# rrfdc.net
KiCad netlist of a schematic drawn in EAGLE
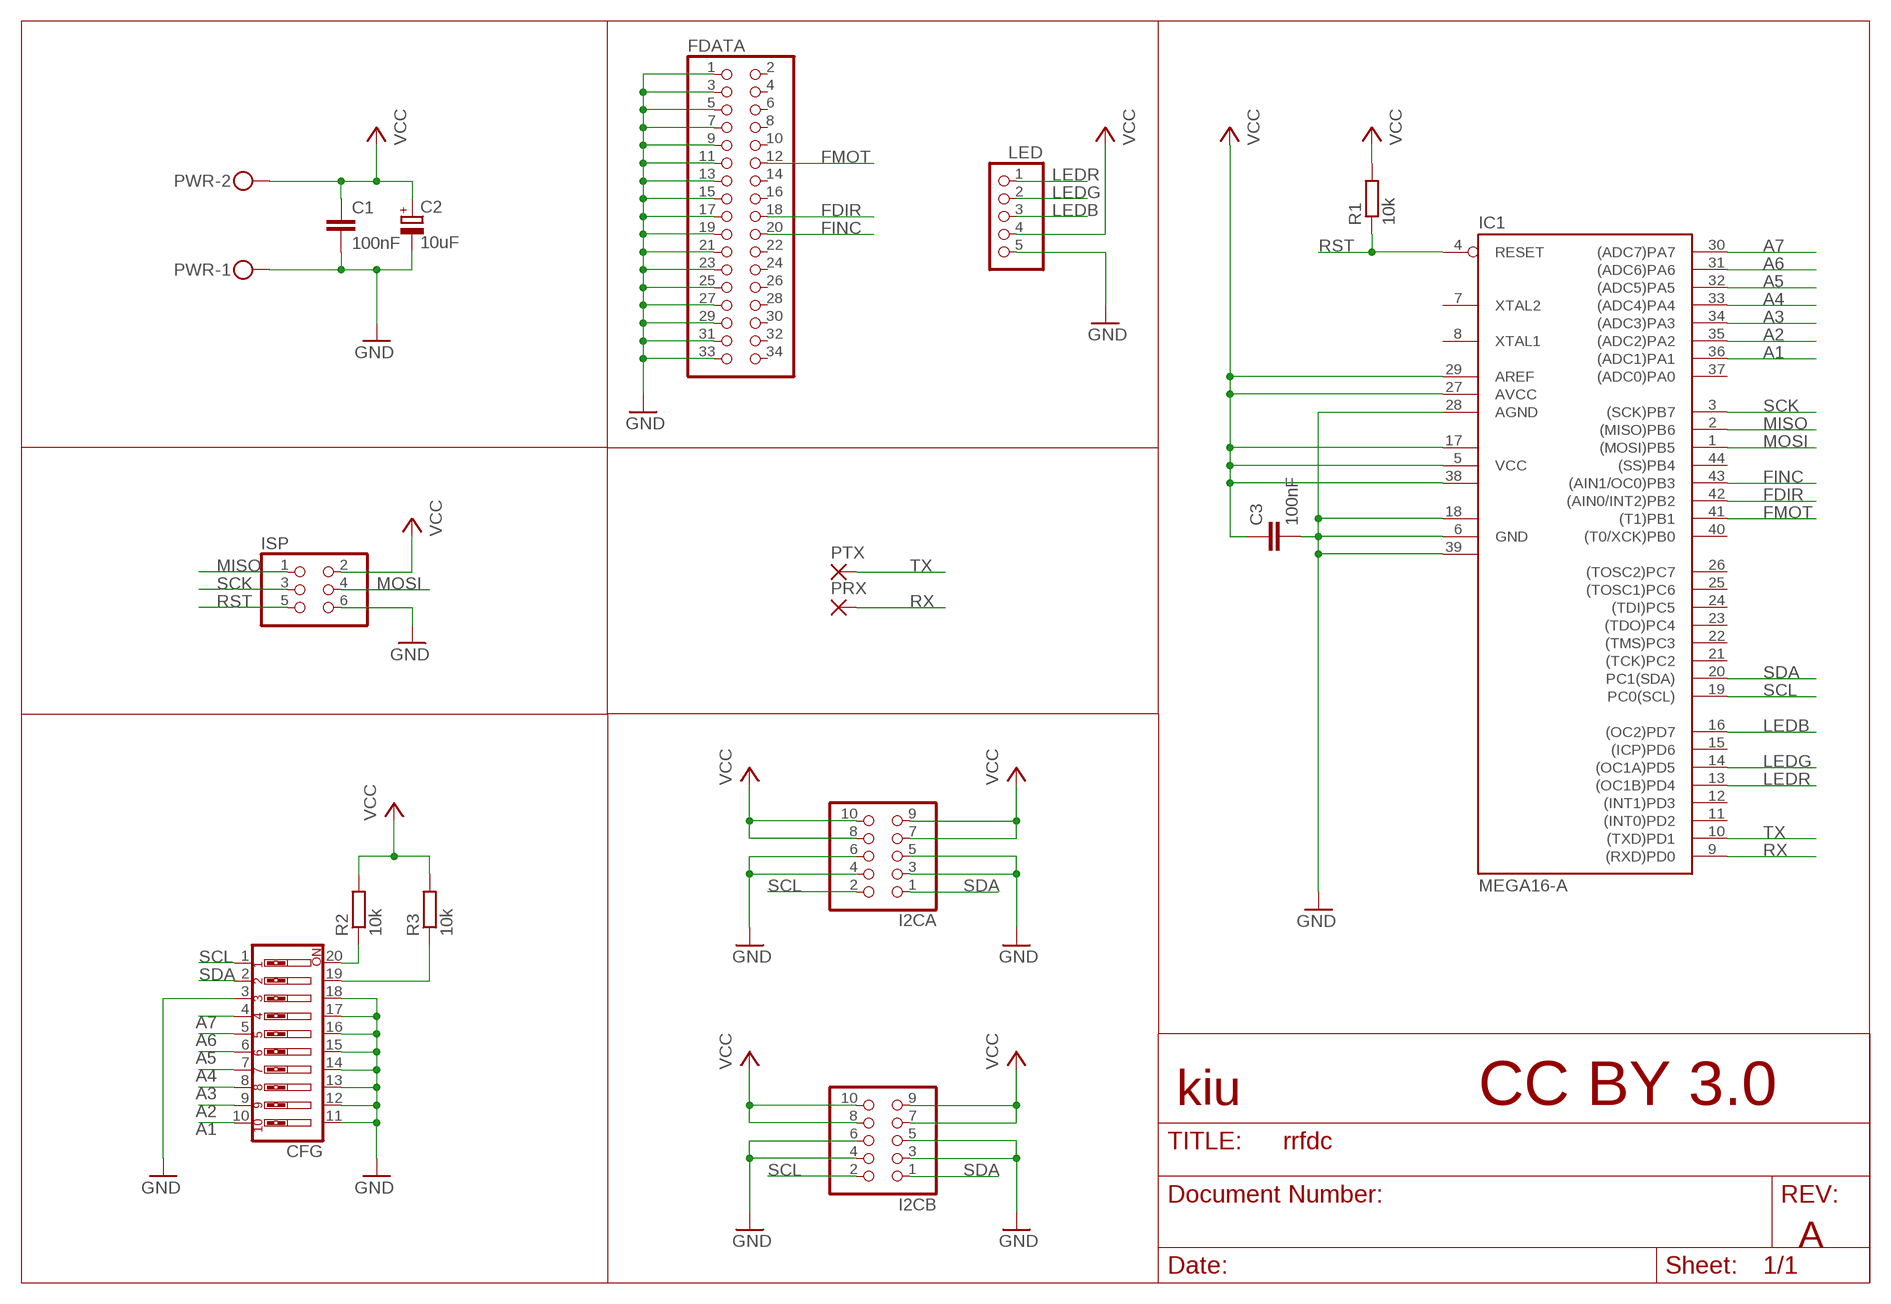
[diagram p0: schematic, sheet 1]

(export (version "E")
  (design (tool "Eeschema 10.0.6"))
  (components
    (comp (ref "C1")
      (value "100nF")
      (footprint "eagle-import:C0805")
      (libsource (lib "eagle-import") (part "C-EUC0805"))
    )
    (comp (ref "C2")
      (value "10uF")
      (footprint "eagle-import:CT3216")
      (libsource (lib "eagle-import") (part "CPOL-EUCT3216"))
    )
    (comp (ref "C3")
      (value "100nF")
      (footprint "eagle-import:C0805")
      (libsource (lib "eagle-import") (part "C-EUC0805"))
    )
    (comp (ref "CFG")
      (value "SW_DIP-10")
      (footprint "eagle-import:EDG-10")
      (libsource (lib "eagle-import") (part "SW_DIP-10"))
    )
    (comp (ref "FDATA")
      (value "PINHD-2X17")
      (footprint "eagle-import:2X17")
      (libsource (lib "eagle-import") (part "PINHD-2X17"))
    )
    (comp (ref "I2CA")
      (value "PINHD-2X5")
      (footprint "eagle-import:2X05")
      (libsource (lib "eagle-import") (part "PINHD-2X5"))
    )
    (comp (ref "I2CB")
      (value "PINHD-2X5")
      (footprint "eagle-import:2X05")
      (libsource (lib "eagle-import") (part "PINHD-2X5"))
    )
    (comp (ref "IC1")
      (value "MEGA16-A")
      (footprint "eagle-import:TQFP44")
      (libsource (lib "eagle-import") (part "MEGA16-A"))
    )
    (comp (ref "ISP")
      (value "PINHD-2X3")
      (footprint "eagle-import:2X03")
      (libsource (lib "eagle-import") (part "PINHD-2X3"))
    )
    (comp (ref "LED")
      (value "PINHD-1X5")
      (footprint "eagle-import:1X05")
      (libsource (lib "eagle-import") (part "PINHD-1X5"))
    )
    (comp (ref "PRX")
      (value "SMD2")
      (footprint "eagle-import:SMD1,27-2,54")
      (libsource (lib "eagle-import") (part "SMD2"))
    )
    (comp (ref "PTX")
      (value "SMD2")
      (footprint "eagle-import:SMD1,27-2,54")
      (libsource (lib "eagle-import") (part "SMD2"))
    )
    (comp (ref "PWR")
      (value "MKDSN1,5/2-5,08")
      (footprint "eagle-import:MKDSN1,5_2-5,08")
      (fields (field (name "MPN") "MKDSN 1,5/2-5.08"))
      (libsource (lib "eagle-import") (part "MKDSN1,5/2-5,08"))
    )
    (comp (ref "R1")
      (value "10k")
      (footprint "eagle-import:R0805")
      (libsource (lib "eagle-import") (part "R-EU_R0805"))
    )
    (comp (ref "R2")
      (value "10k")
      (footprint "eagle-import:R0805")
      (libsource (lib "eagle-import") (part "R-EU_R0805"))
    )
    (comp (ref "R3")
      (value "10k")
      (footprint "eagle-import:R0805")
      (libsource (lib "eagle-import") (part "R-EU_R0805"))
    )
  )
  (nets
    (net (code "1") (name "/A1") (class "Default")
      (node (ref "CFG") (pin "10") (pinfunction "10_10") (pintype "passive"))
      (node (ref "IC1") (pin "36") (pinfunction "(ADC1)PA1_36") (pintype "bidirectional"))
    )
    (net (code "2") (name "/A2") (class "Default")
      (node (ref "CFG") (pin "9") (pinfunction "9_9") (pintype "passive"))
      (node (ref "IC1") (pin "35") (pinfunction "(ADC2)PA2_35") (pintype "bidirectional"))
    )
    (net (code "3") (name "/A3") (class "Default")
      (node (ref "CFG") (pin "8") (pinfunction "8_8") (pintype "passive"))
      (node (ref "IC1") (pin "34") (pinfunction "(ADC3)PA3_34") (pintype "bidirectional"))
    )
    (net (code "4") (name "/A4") (class "Default")
      (node (ref "CFG") (pin "7") (pinfunction "7_7") (pintype "passive"))
      (node (ref "IC1") (pin "33") (pinfunction "(ADC4)PA4_33") (pintype "bidirectional"))
    )
    (net (code "5") (name "/A5") (class "Default")
      (node (ref "CFG") (pin "6") (pinfunction "6_6") (pintype "passive"))
      (node (ref "IC1") (pin "32") (pinfunction "(ADC5)PA5_32") (pintype "bidirectional"))
    )
    (net (code "6") (name "/A6") (class "Default")
      (node (ref "CFG") (pin "5") (pinfunction "5_5") (pintype "passive"))
      (node (ref "IC1") (pin "31") (pinfunction "(ADC6)PA6_31") (pintype "bidirectional"))
    )
    (net (code "7") (name "/A7") (class "Default")
      (node (ref "CFG") (pin "4") (pinfunction "4_4") (pintype "passive"))
      (node (ref "IC1") (pin "30") (pinfunction "(ADC7)PA7_30") (pintype "bidirectional"))
    )
    (net (code "8") (name "/FDIR") (class "Default")
      (node (ref "FDATA") (pin "18") (pinfunction "18_18") (pintype "passive"))
      (node (ref "IC1") (pin "42") (pinfunction "(AIN0/INT2)PB2_42") (pintype "bidirectional"))
    )
    (net (code "9") (name "/FINC") (class "Default")
      (node (ref "FDATA") (pin "20") (pinfunction "20_20") (pintype "passive"))
      (node (ref "IC1") (pin "43") (pinfunction "(AIN1/OC0)PB3_43") (pintype "bidirectional"))
    )
    (net (code "10") (name "/FMOT") (class "Default")
      (node (ref "FDATA") (pin "12") (pinfunction "12_12") (pintype "passive"))
      (node (ref "IC1") (pin "41") (pinfunction "(T1)PB1_41") (pintype "bidirectional"))
    )
    (net (code "11") (name "/LEDB") (class "Default")
      (node (ref "IC1") (pin "16") (pinfunction "(OC2)PD7_16") (pintype "bidirectional"))
      (node (ref "LED") (pin "3") (pinfunction "3_3") (pintype "passive"))
    )
    (net (code "12") (name "/LEDG") (class "Default")
      (node (ref "IC1") (pin "14") (pinfunction "(OC1A)PD5_14") (pintype "bidirectional"))
      (node (ref "LED") (pin "2") (pinfunction "2_2") (pintype "passive"))
    )
    (net (code "13") (name "/LEDR") (class "Default")
      (node (ref "IC1") (pin "13") (pinfunction "(OC1B)PD4_13") (pintype "bidirectional"))
      (node (ref "LED") (pin "1") (pinfunction "1_1") (pintype "passive"))
    )
    (net (code "14") (name "/MISO") (class "Default")
      (node (ref "IC1") (pin "2") (pinfunction "(MISO)PB6_2") (pintype "bidirectional"))
      (node (ref "ISP") (pin "1") (pinfunction "1_1") (pintype "passive"))
    )
    (net (code "15") (name "/MOSI") (class "Default")
      (node (ref "IC1") (pin "1") (pinfunction "(MOSI)PB5_1") (pintype "bidirectional"))
      (node (ref "ISP") (pin "4") (pinfunction "4_4") (pintype "passive"))
    )
    (net (code "16") (name "/RST") (class "Default")
      (node (ref "IC1") (pin "4") (pinfunction "RESET_4") (pintype "input"))
      (node (ref "ISP") (pin "5") (pinfunction "5_5") (pintype "passive"))
      (node (ref "R1") (pin "1") (pinfunction "1_1") (pintype "passive"))
    )
    (net (code "17") (name "/RX") (class "Default")
      (node (ref "IC1") (pin "9") (pinfunction "(RXD)PD0_9") (pintype "bidirectional"))
      (node (ref "PRX") (pin "1") (pinfunction "P_1") (pintype "passive"))
    )
    (net (code "18") (name "/SCK") (class "Default")
      (node (ref "IC1") (pin "3") (pinfunction "(SCK)PB7_3") (pintype "bidirectional"))
      (node (ref "ISP") (pin "3") (pinfunction "3_3") (pintype "passive"))
    )
    (net (code "19") (name "/SCL") (class "Default")
      (node (ref "CFG") (pin "1") (pinfunction "1_1") (pintype "passive"))
      (node (ref "I2CA") (pin "2") (pinfunction "2_2") (pintype "passive"))
      (node (ref "I2CB") (pin "2") (pinfunction "2_2") (pintype "passive"))
      (node (ref "IC1") (pin "19") (pinfunction "PC0(SCL)_19") (pintype "bidirectional"))
    )
    (net (code "20") (name "/SDA") (class "Default")
      (node (ref "CFG") (pin "2") (pinfunction "2_2") (pintype "passive"))
      (node (ref "I2CA") (pin "1") (pinfunction "1_1") (pintype "passive"))
      (node (ref "I2CB") (pin "1") (pinfunction "1_1") (pintype "passive"))
      (node (ref "IC1") (pin "20") (pinfunction "PC1(SDA)_20") (pintype "bidirectional"))
    )
    (net (code "21") (name "/TX") (class "Default")
      (node (ref "IC1") (pin "10") (pinfunction "(TXD)PD1_10") (pintype "bidirectional"))
      (node (ref "PTX") (pin "1") (pinfunction "P_1") (pintype "passive"))
    )
    (net (code "22") (name "GND") (class "Default")
      (node (ref "C1") (pin "2") (pinfunction "2_2") (pintype "passive"))
      (node (ref "C2") (pin "-") (pinfunction "-_-") (pintype "passive"))
      (node (ref "C3") (pin "2") (pinfunction "2_2") (pintype "passive"))
      (node (ref "CFG") (pin "11") (pinfunction "11_11") (pintype "passive"))
      (node (ref "CFG") (pin "12") (pinfunction "12_12") (pintype "passive"))
      (node (ref "CFG") (pin "13") (pinfunction "13_13") (pintype "passive"))
      (node (ref "CFG") (pin "14") (pinfunction "14_14") (pintype "passive"))
      (node (ref "CFG") (pin "15") (pinfunction "15_15") (pintype "passive"))
      (node (ref "CFG") (pin "16") (pinfunction "16_16") (pintype "passive"))
      (node (ref "CFG") (pin "17") (pinfunction "17_17") (pintype "passive"))
      (node (ref "CFG") (pin "18") (pinfunction "18_18") (pintype "passive"))
      (node (ref "CFG") (pin "3") (pinfunction "3_3") (pintype "passive"))
      (node (ref "FDATA") (pin "1") (pinfunction "1_1") (pintype "passive"))
      (node (ref "FDATA") (pin "11") (pinfunction "11_11") (pintype "passive"))
      (node (ref "FDATA") (pin "13") (pinfunction "13_13") (pintype "passive"))
      (node (ref "FDATA") (pin "15") (pinfunction "15_15") (pintype "passive"))
      (node (ref "FDATA") (pin "17") (pinfunction "17_17") (pintype "passive"))
      (node (ref "FDATA") (pin "19") (pinfunction "19_19") (pintype "passive"))
      (node (ref "FDATA") (pin "21") (pinfunction "21_21") (pintype "passive"))
      (node (ref "FDATA") (pin "23") (pinfunction "23_23") (pintype "passive"))
      (node (ref "FDATA") (pin "25") (pinfunction "25_25") (pintype "passive"))
      (node (ref "FDATA") (pin "27") (pinfunction "27_27") (pintype "passive"))
      (node (ref "FDATA") (pin "29") (pinfunction "29_29") (pintype "passive"))
      (node (ref "FDATA") (pin "3") (pinfunction "3_3") (pintype "passive"))
      (node (ref "FDATA") (pin "31") (pinfunction "31_31") (pintype "passive"))
      (node (ref "FDATA") (pin "33") (pinfunction "33_33") (pintype "passive"))
      (node (ref "FDATA") (pin "5") (pinfunction "5_5") (pintype "passive"))
      (node (ref "FDATA") (pin "7") (pinfunction "7_7") (pintype "passive"))
      (node (ref "FDATA") (pin "9") (pinfunction "9_9") (pintype "passive"))
      (node (ref "I2CA") (pin "3") (pinfunction "3_3") (pintype "passive"))
      (node (ref "I2CA") (pin "4") (pinfunction "4_4") (pintype "passive"))
      (node (ref "I2CA") (pin "5") (pinfunction "5_5") (pintype "passive"))
      (node (ref "I2CA") (pin "6") (pinfunction "6_6") (pintype "passive"))
      (node (ref "I2CB") (pin "3") (pinfunction "3_3") (pintype "passive"))
      (node (ref "I2CB") (pin "4") (pinfunction "4_4") (pintype "passive"))
      (node (ref "I2CB") (pin "5") (pinfunction "5_5") (pintype "passive"))
      (node (ref "I2CB") (pin "6") (pinfunction "6_6") (pintype "passive"))
      (node (ref "IC1") (pin "18") (pinfunction "GND1_18") (pintype "power_in"))
      (node (ref "IC1") (pin "28") (pinfunction "AGND_28") (pintype "power_in"))
      (node (ref "IC1") (pin "39") (pinfunction "GND2_39") (pintype "power_in"))
      (node (ref "IC1") (pin "6") (pinfunction "GND_6") (pintype "power_in"))
      (node (ref "ISP") (pin "6") (pinfunction "6_6") (pintype "passive"))
      (node (ref "LED") (pin "5") (pinfunction "5_5") (pintype "passive"))
      (node (ref "PWR") (pin "1") (pinfunction "KL_1") (pintype "passive"))
    )
    (net (code "23") (name "Net-(CFG-Pad19)") (class "Default")
      (node (ref "CFG") (pin "19") (pinfunction "19_19") (pintype "passive"))
      (node (ref "R3") (pin "1") (pinfunction "1_1") (pintype "passive"))
    )
    (net (code "24") (name "Net-(CFG-Pad20)") (class "Default")
      (node (ref "CFG") (pin "20") (pinfunction "20_20") (pintype "passive"))
      (node (ref "R2") (pin "1") (pinfunction "1_1") (pintype "passive"))
    )
    (net (code "25") (name "VCC") (class "Default")
      (node (ref "C1") (pin "1") (pinfunction "1_1") (pintype "passive"))
      (node (ref "C2") (pin "+") (pinfunction "+_+") (pintype "passive"))
      (node (ref "C3") (pin "1") (pinfunction "1_1") (pintype "passive"))
      (node (ref "I2CA") (pin "10") (pinfunction "10_10") (pintype "passive"))
      (node (ref "I2CA") (pin "7") (pinfunction "7_7") (pintype "passive"))
      (node (ref "I2CA") (pin "8") (pinfunction "8_8") (pintype "passive"))
      (node (ref "I2CA") (pin "9") (pinfunction "9_9") (pintype "passive"))
      (node (ref "I2CB") (pin "10") (pinfunction "10_10") (pintype "passive"))
      (node (ref "I2CB") (pin "7") (pinfunction "7_7") (pintype "passive"))
      (node (ref "I2CB") (pin "8") (pinfunction "8_8") (pintype "passive"))
      (node (ref "I2CB") (pin "9") (pinfunction "9_9") (pintype "passive"))
      (node (ref "IC1") (pin "17") (pinfunction "VCC1_17") (pintype "power_in"))
      (node (ref "IC1") (pin "27") (pinfunction "AVCC_27") (pintype "power_in"))
      (node (ref "IC1") (pin "29") (pinfunction "AREF_29") (pintype "power_in"))
      (node (ref "IC1") (pin "38") (pinfunction "VCC2_38") (pintype "power_in"))
      (node (ref "IC1") (pin "5") (pinfunction "VCC_5") (pintype "power_in"))
      (node (ref "ISP") (pin "2") (pinfunction "2_2") (pintype "passive"))
      (node (ref "LED") (pin "4") (pinfunction "4_4") (pintype "passive"))
      (node (ref "PWR") (pin "2") (pinfunction "KL_2") (pintype "passive"))
      (node (ref "R1") (pin "2") (pinfunction "2_2") (pintype "passive"))
      (node (ref "R2") (pin "2") (pinfunction "2_2") (pintype "passive"))
      (node (ref "R3") (pin "2") (pinfunction "2_2") (pintype "passive"))
    )
    (net (code "26") (name "unconnected-(FDATA-Pad2)") (class "Default")
      (node (ref "FDATA") (pin "2") (pinfunction "2_2") (pintype "passive"))
    )
    (net (code "27") (name "unconnected-(FDATA-Pad4)") (class "Default")
      (node (ref "FDATA") (pin "4") (pinfunction "4_4") (pintype "passive"))
    )
    (net (code "28") (name "unconnected-(FDATA-Pad6)") (class "Default")
      (node (ref "FDATA") (pin "6") (pinfunction "6_6") (pintype "passive"))
    )
    (net (code "29") (name "unconnected-(FDATA-Pad8)") (class "Default")
      (node (ref "FDATA") (pin "8") (pinfunction "8_8") (pintype "passive"))
    )
    (net (code "30") (name "unconnected-(FDATA-Pad10)") (class "Default")
      (node (ref "FDATA") (pin "10") (pinfunction "10_10") (pintype "passive"))
    )
    (net (code "31") (name "unconnected-(FDATA-Pad14)") (class "Default")
      (node (ref "FDATA") (pin "14") (pinfunction "14_14") (pintype "passive"))
    )
    (net (code "32") (name "unconnected-(FDATA-Pad16)") (class "Default")
      (node (ref "FDATA") (pin "16") (pinfunction "16_16") (pintype "passive"))
    )
    (net (code "33") (name "unconnected-(FDATA-Pad22)") (class "Default")
      (node (ref "FDATA") (pin "22") (pinfunction "22_22") (pintype "passive"))
    )
    (net (code "34") (name "unconnected-(FDATA-Pad24)") (class "Default")
      (node (ref "FDATA") (pin "24") (pinfunction "24_24") (pintype "passive"))
    )
    (net (code "35") (name "unconnected-(FDATA-Pad26)") (class "Default")
      (node (ref "FDATA") (pin "26") (pinfunction "26_26") (pintype "passive"))
    )
    (net (code "36") (name "unconnected-(FDATA-Pad28)") (class "Default")
      (node (ref "FDATA") (pin "28") (pinfunction "28_28") (pintype "passive"))
    )
    (net (code "37") (name "unconnected-(FDATA-Pad30)") (class "Default")
      (node (ref "FDATA") (pin "30") (pinfunction "30_30") (pintype "passive"))
    )
    (net (code "38") (name "unconnected-(FDATA-Pad32)") (class "Default")
      (node (ref "FDATA") (pin "32") (pinfunction "32_32") (pintype "passive"))
    )
    (net (code "39") (name "unconnected-(FDATA-Pad34)") (class "Default")
      (node (ref "FDATA") (pin "34") (pinfunction "34_34") (pintype "passive"))
    )
    (net (code "40") (name "unconnected-(IC1-(ADC0)PA0-Pad37)") (class "Default")
      (node (ref "IC1") (pin "37") (pinfunction "(ADC0)PA0_37") (pintype "bidirectional"))
    )
    (net (code "41") (name "unconnected-(IC1-(ICP)PD6-Pad15)") (class "Default")
      (node (ref "IC1") (pin "15") (pinfunction "(ICP)PD6_15") (pintype "bidirectional"))
    )
    (net (code "42") (name "unconnected-(IC1-(INT0)PD2-Pad11)") (class "Default")
      (node (ref "IC1") (pin "11") (pinfunction "(INT0)PD2_11") (pintype "bidirectional"))
    )
    (net (code "43") (name "unconnected-(IC1-(INT1)PD3-Pad12)") (class "Default")
      (node (ref "IC1") (pin "12") (pinfunction "(INT1)PD3_12") (pintype "bidirectional"))
    )
    (net (code "44") (name "unconnected-(IC1-(SS)PB4-Pad44)") (class "Default")
      (node (ref "IC1") (pin "44") (pinfunction "(SS)PB4_44") (pintype "bidirectional"))
    )
    (net (code "45") (name "unconnected-(IC1-(T0{slash}XCK)PB0-Pad40)") (class "Default")
      (node (ref "IC1") (pin "40") (pinfunction "(T0/XCK)PB0_40") (pintype "bidirectional"))
    )
    (net (code "46") (name "unconnected-(IC1-(TCK)PC2-Pad21)") (class "Default")
      (node (ref "IC1") (pin "21") (pinfunction "(TCK)PC2_21") (pintype "bidirectional"))
    )
    (net (code "47") (name "unconnected-(IC1-(TDI)PC5-Pad24)") (class "Default")
      (node (ref "IC1") (pin "24") (pinfunction "(TDI)PC5_24") (pintype "bidirectional"))
    )
    (net (code "48") (name "unconnected-(IC1-(TDO)PC4-Pad23)") (class "Default")
      (node (ref "IC1") (pin "23") (pinfunction "(TDO)PC4_23") (pintype "bidirectional"))
    )
    (net (code "49") (name "unconnected-(IC1-(TMS)PC3-Pad22)") (class "Default")
      (node (ref "IC1") (pin "22") (pinfunction "(TMS)PC3_22") (pintype "bidirectional"))
    )
    (net (code "50") (name "unconnected-(IC1-(TOSC1)PC6-Pad25)") (class "Default")
      (node (ref "IC1") (pin "25") (pinfunction "(TOSC1)PC6_25") (pintype "bidirectional"))
    )
    (net (code "51") (name "unconnected-(IC1-(TOSC2)PC7-Pad26)") (class "Default")
      (node (ref "IC1") (pin "26") (pinfunction "(TOSC2)PC7_26") (pintype "bidirectional"))
    )
    (net (code "52") (name "unconnected-(IC1-XTAL1-Pad8)") (class "Default")
      (node (ref "IC1") (pin "8") (pinfunction "XTAL1_8") (pintype "bidirectional"))
    )
    (net (code "53") (name "unconnected-(IC1-XTAL2-Pad7)") (class "Default")
      (node (ref "IC1") (pin "7") (pinfunction "XTAL2_7") (pintype "bidirectional"))
    )
  )
)
